# PLA_Sticks_Gen2_Rev4.net
KiCad netlist of a schematic drawn in EAGLE
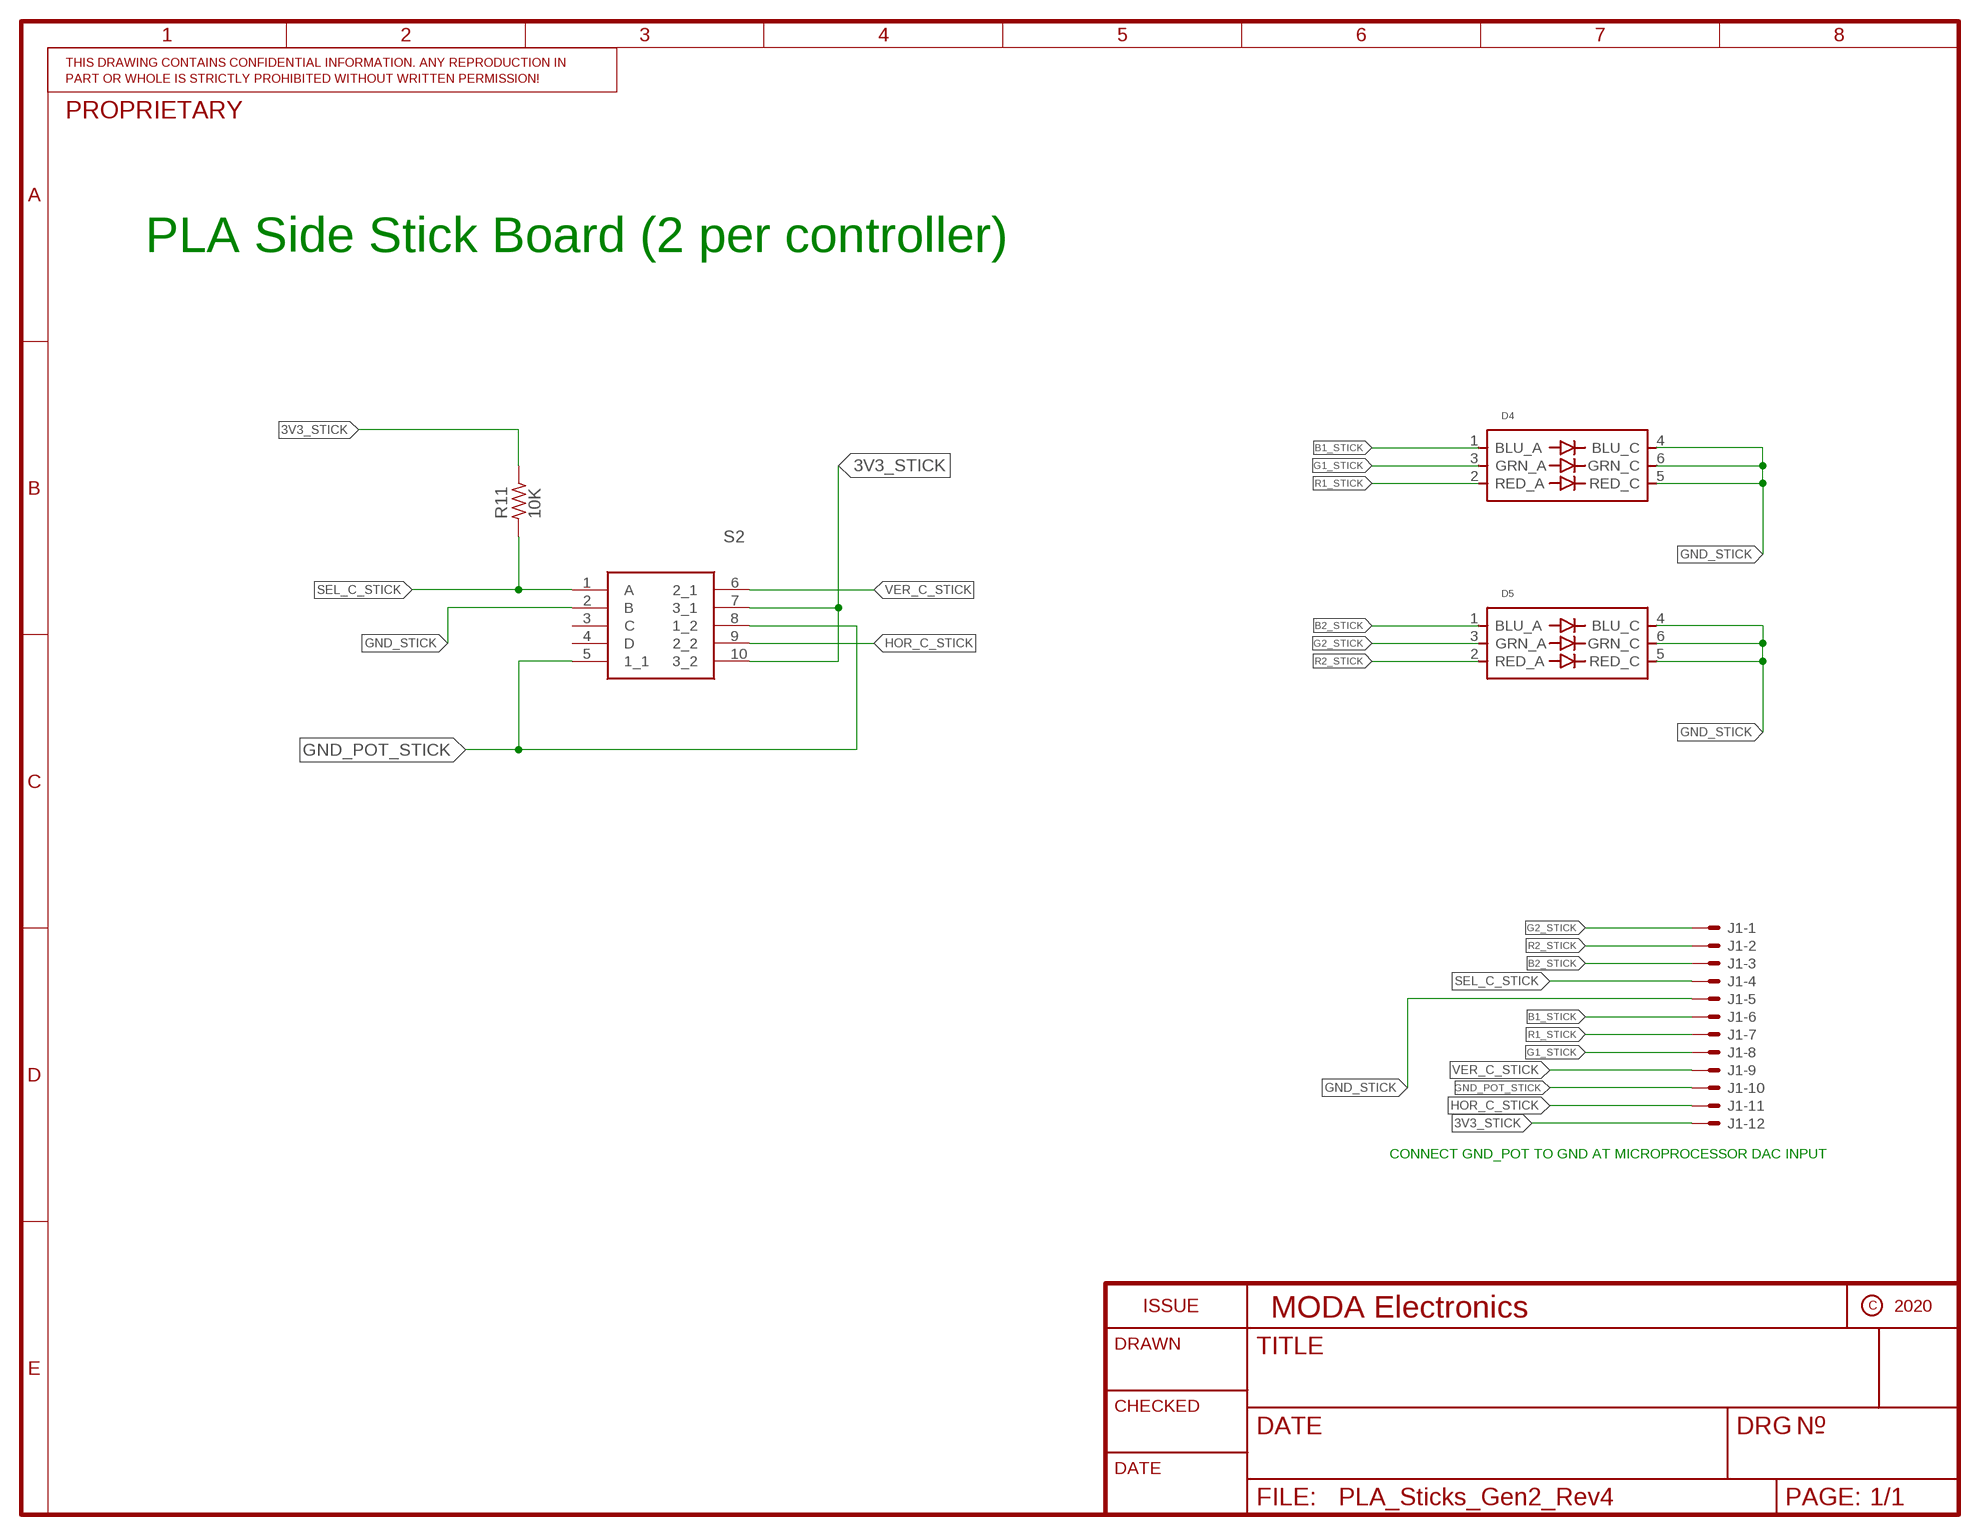
[diagram p0: schematic, sheet 1]

(export (version "E")
  (design (tool "Eeschema 10.0.6"))
  (components
    (comp (ref "D4")
      (value "XZFBBM2ACRDG92W-3")
      (footprint "eagle-import:XZFBBM2ACRDG92W-3")
      (libsource (lib "eagle-import") (part "XZFBBM2ACRDG92W-3"))
    )
    (comp (ref "D5")
      (value "XZFBBM2ACRDG92W-3")
      (footprint "eagle-import:XZFBBM2ACRDG92W-3")
      (libsource (lib "eagle-import") (part "XZFBBM2ACRDG92W-3"))
    )
    (comp (ref "J1")
      (value "SM12B-SSR-H-TB")
      (footprint "eagle-import:SM12B-SSR-H-TB")
      (fields (field (name "PARTNO") "BM12B-SRSS-TB(LF)(SN)"))
      (libsource (lib "eagle-import") (part "SM12B-SSR-H-TB"))
    )
    (comp (ref "R11")
      (value "10K")
      (footprint "eagle-import:R0603")
      (fields (field (name "PARTNO") "ERJ-2GEJ103X"))
      (libsource (lib "eagle-import") (part "R_0603"))
    )
    (comp (ref "S2")
      (value "RKJXV1224005")
      (footprint "eagle-import:RKJXV1224005")
      (fields
        (field (name "MOUSER_PART_NUMBER") "688-RKJXV1224005")
        (field (name "RS_PART_NUMBER") "1239578")
      )
      (libsource (lib "eagle-import") (part "RKJXV1224005"))
    )
  )
  (nets
    (net (code "1") (name "3V3_STICK") (class "Default")
      (node (ref "J1") (pin "12") (pinfunction "S_12") (pintype "passive"))
      (node (ref "R11") (pin "2") (pinfunction "2_2") (pintype "passive"))
      (node (ref "S2") (pin "10") (pinfunction "3_2_10") (pintype "bidirectional"))
      (node (ref "S2") (pin "7") (pinfunction "3_1_7") (pintype "bidirectional"))
    )
    (net (code "2") (name "B1_STICK") (class "Default")
      (node (ref "D4") (pin "1") (pinfunction "BLU_A_1") (pintype "bidirectional"))
      (node (ref "J1") (pin "6") (pinfunction "S_6") (pintype "passive"))
    )
    (net (code "3") (name "B2_STICK") (class "Default")
      (node (ref "D5") (pin "1") (pinfunction "BLU_A_1") (pintype "bidirectional"))
      (node (ref "J1") (pin "3") (pinfunction "S_3") (pintype "passive"))
    )
    (net (code "4") (name "G1_STICK") (class "Default")
      (node (ref "D4") (pin "3") (pinfunction "GRN_A_3") (pintype "bidirectional"))
      (node (ref "J1") (pin "8") (pinfunction "S_8") (pintype "passive"))
    )
    (net (code "5") (name "G2_STICK") (class "Default")
      (node (ref "D5") (pin "3") (pinfunction "GRN_A_3") (pintype "bidirectional"))
      (node (ref "J1") (pin "1") (pinfunction "S_1") (pintype "passive"))
    )
    (net (code "6") (name "GND_POT_STICK") (class "Default")
      (node (ref "J1") (pin "10") (pinfunction "S_10") (pintype "passive"))
      (node (ref "S2") (pin "5") (pinfunction "1_1_5") (pintype "bidirectional"))
      (node (ref "S2") (pin "8") (pinfunction "1_2_8") (pintype "bidirectional"))
    )
    (net (code "7") (name "GND_STICK") (class "Default")
      (node (ref "D4") (pin "4") (pinfunction "BLU_C_4") (pintype "bidirectional"))
      (node (ref "D4") (pin "5") (pinfunction "RED_C_5") (pintype "bidirectional"))
      (node (ref "D4") (pin "6") (pinfunction "GRN_C_6") (pintype "bidirectional"))
      (node (ref "D5") (pin "4") (pinfunction "BLU_C_4") (pintype "bidirectional"))
      (node (ref "D5") (pin "5") (pinfunction "RED_C_5") (pintype "bidirectional"))
      (node (ref "D5") (pin "6") (pinfunction "GRN_C_6") (pintype "bidirectional"))
      (node (ref "J1") (pin "5") (pinfunction "S_5") (pintype "passive"))
      (node (ref "S2") (pin "2") (pinfunction "B_2") (pintype "bidirectional"))
    )
    (net (code "8") (name "HOR_C_STICK") (class "Default")
      (node (ref "J1") (pin "11") (pinfunction "S_11") (pintype "passive"))
      (node (ref "S2") (pin "9") (pinfunction "2_2_9") (pintype "bidirectional"))
    )
    (net (code "9") (name "R1_STICK") (class "Default")
      (node (ref "D4") (pin "2") (pinfunction "RED_A_2") (pintype "bidirectional"))
      (node (ref "J1") (pin "7") (pinfunction "S_7") (pintype "passive"))
    )
    (net (code "10") (name "R2_STICK") (class "Default")
      (node (ref "D5") (pin "2") (pinfunction "RED_A_2") (pintype "bidirectional"))
      (node (ref "J1") (pin "2") (pinfunction "S_2") (pintype "passive"))
    )
    (net (code "11") (name "SEL_C_STICK") (class "Default")
      (node (ref "J1") (pin "4") (pinfunction "S_4") (pintype "passive"))
      (node (ref "R11") (pin "1") (pinfunction "1_1") (pintype "passive"))
      (node (ref "S2") (pin "1") (pinfunction "A_1") (pintype "bidirectional"))
    )
    (net (code "12") (name "VER_C_STICK") (class "Default")
      (node (ref "J1") (pin "9") (pinfunction "S_9") (pintype "passive"))
      (node (ref "S2") (pin "6") (pinfunction "2_1_6") (pintype "bidirectional"))
    )
    (net (code "13") (name "unconnected-(S2-C-Pad3)") (class "Default")
      (node (ref "S2") (pin "3") (pinfunction "C_3") (pintype "bidirectional"))
    )
    (net (code "14") (name "unconnected-(S2-D-Pad4)") (class "Default")
      (node (ref "S2") (pin "4") (pinfunction "D_4") (pintype "bidirectional"))
    )
  )
)
